# Sheet5.net
KiCad netlist of a schematic drawn in Altium Designer
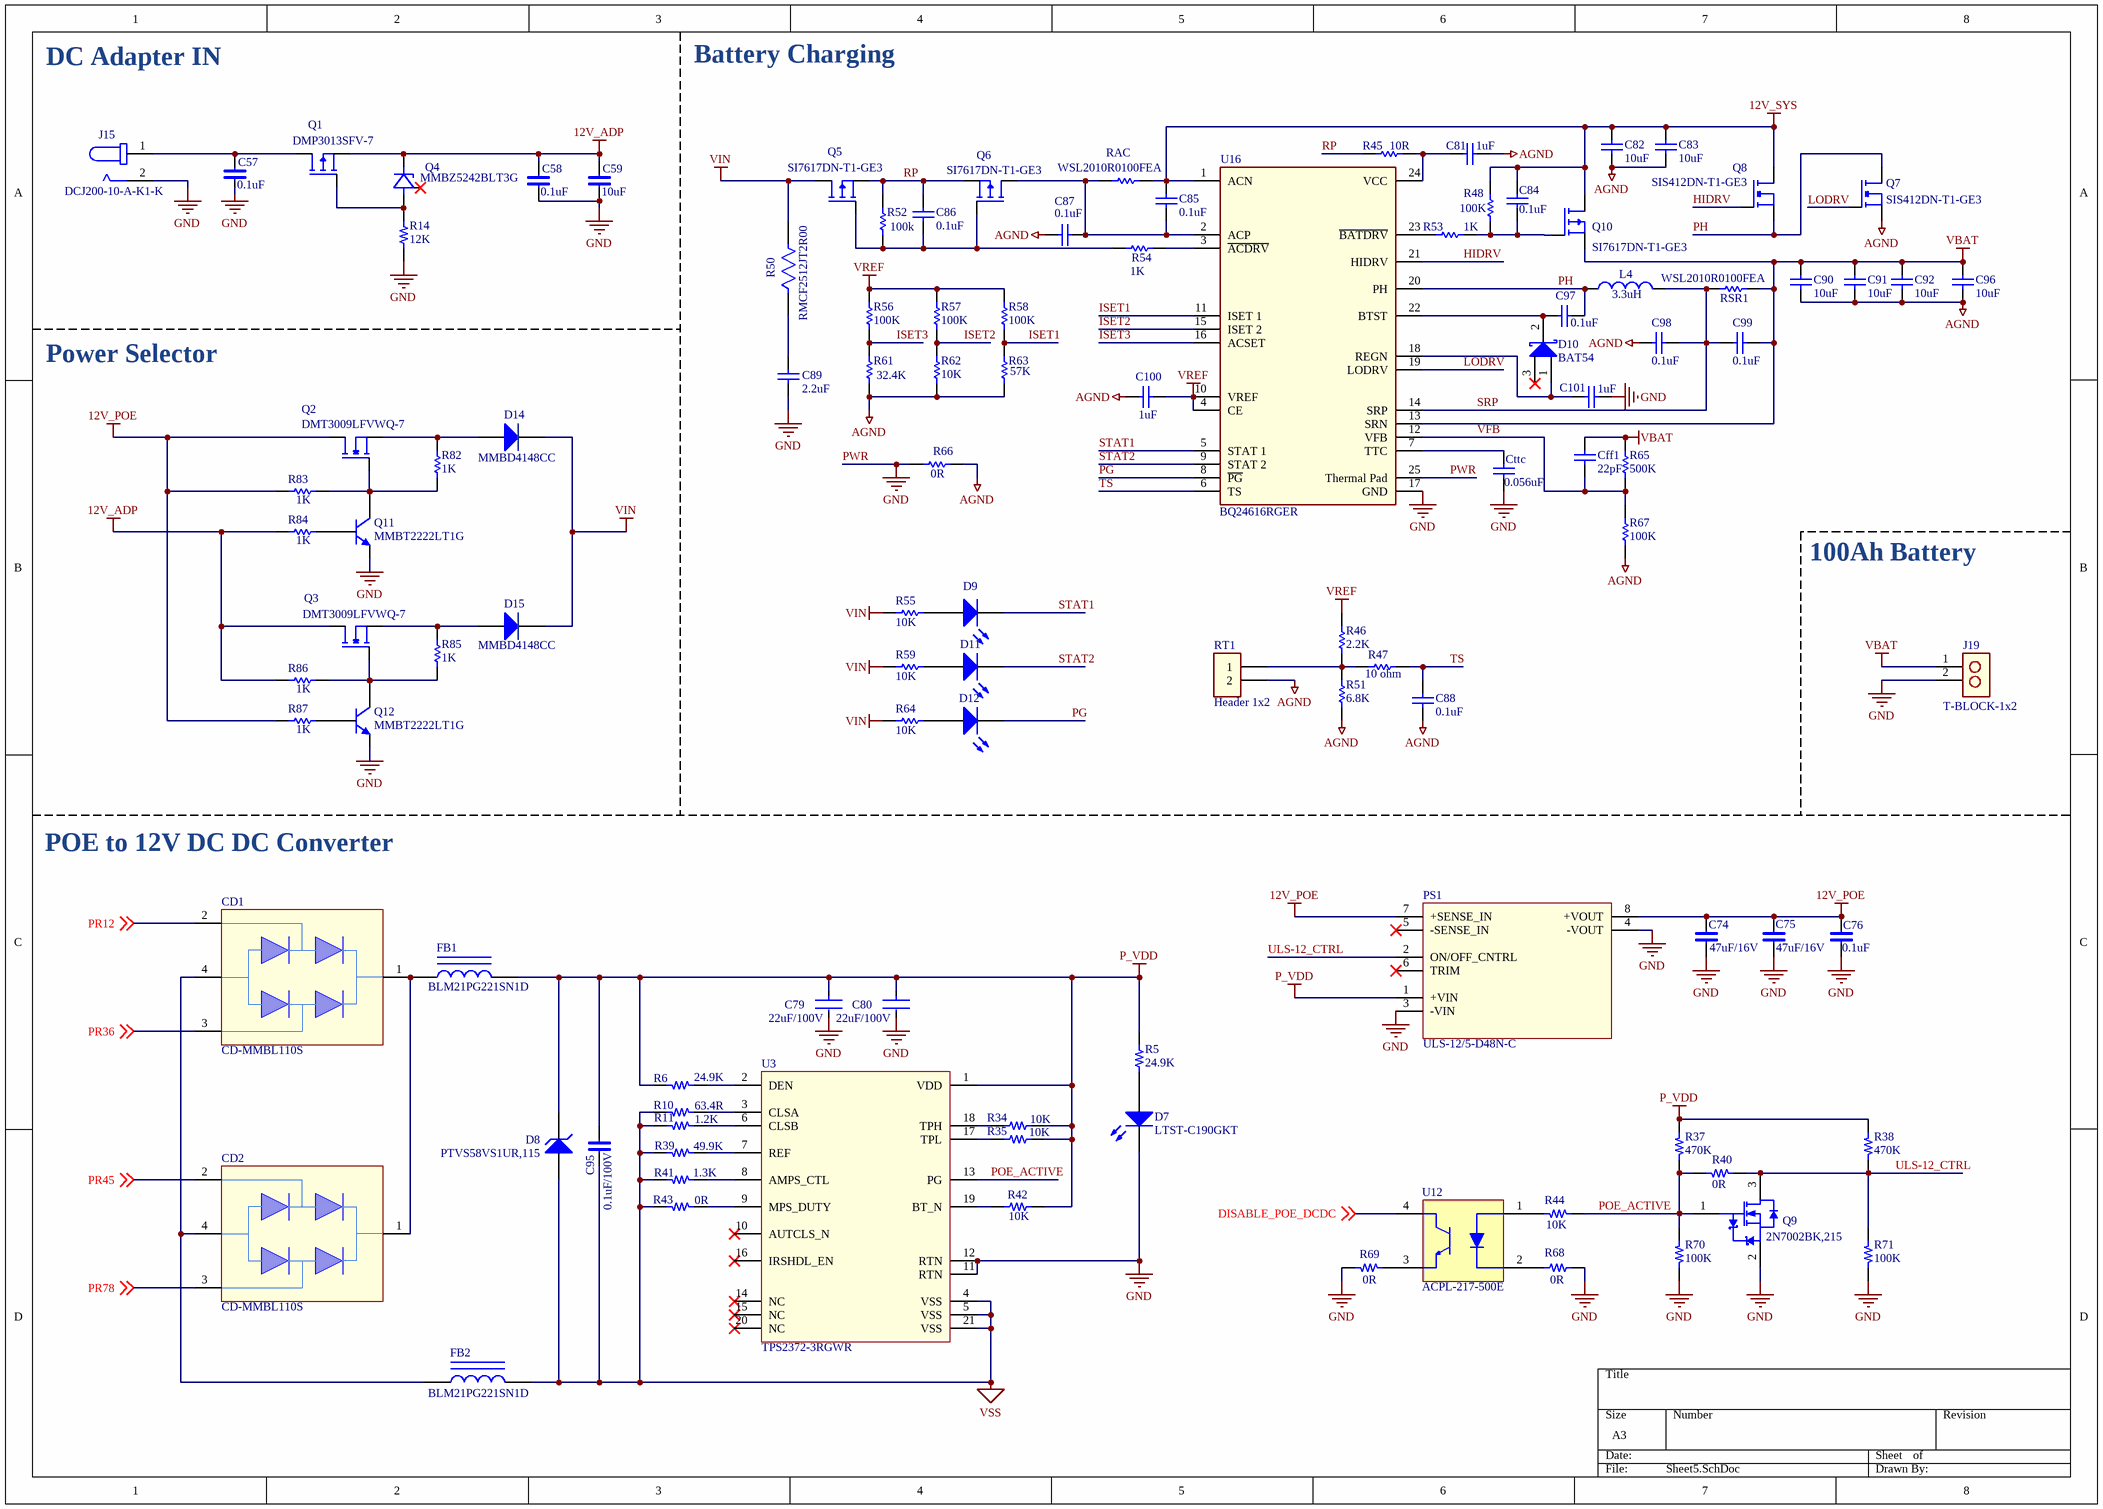
[diagram p0: Sheet5.SchDoc]

(export (version "E")
  (design (tool "Eeschema 10.0.6"))
  (components
    (comp (ref "C57")
      (value "0.1uF")
      (footprint "C-0603/1608")
      (description "CAP CER 10UF 10V X7R 0805")
      (fields (field (name "MFR. PART NO.") "GRM21BR71A106KA73K"))
      (libsource (lib "Custom_Library") (part "Capacitor-NonPolar"))
    )
    (comp (ref "C58")
      (value "0.1uF")
      (footprint "C-0603/1608")
      (description "CAP CER 10UF 10V X7R 0805")
      (fields (field (name "MFR. PART NO.") "GRM21BR71A106KA73K"))
      (libsource (lib "Custom_Library") (part "Capacitor-NonPolar"))
    )
    (comp (ref "C59")
      (value "10uF")
      (footprint "C-1206/3216")
      (description "CAP CER 10UF 10V X7R 0805")
      (fields (field (name "MFR. PART NO.") "GRM21BR71A106KA73K"))
      (libsource (lib "Custom_Library") (part "Capacitor-NonPolar"))
    )
    (comp (ref "C74")
      (value "47uF/16V")
      (footprint "C-1206/3216")
      (description "CAP CER 0.1UF 50V X7R 0402")
      (fields (field (name "MFR. PART NO.") "UMK105B7104KV-FR"))
      (libsource (lib "Custom_Library") (part "Capacitor-NonPolar"))
    )
    (comp (ref "C75")
      (value "47uF/16V")
      (footprint "C-1206/3216")
      (description "CAP CER 0.1UF 50V X7R 0402")
      (fields (field (name "MFR. PART NO.") "UMK105B7104KV-FR"))
      (libsource (lib "Custom_Library") (part "Capacitor-NonPolar"))
    )
    (comp (ref "C76")
      (value "0.1uF")
      (footprint "C-0402/1005")
      (description "CAP CER 0.1UF 50V X7R 0402")
      (fields (field (name "MFR. PART NO.") "UMK105B7104KV-FR"))
      (libsource (lib "Custom_Library") (part "Capacitor-NonPolar"))
    )
    (comp (ref "C79")
      (value "22uF/100V")
      (footprint "FP-KRM55W-6_1_5_3_6_7_1_2-MFG")
      (description "Cap Ceramic 22uF 100V X7R ±15% SMD 2220 +125°C Emboss T/R")
      (fields (field (name "TOLERANCE") "20%"))
      (libsource (lib "Altium Content Vault") (part "02cd4be3c70576c341d710602a673aa"))
    )
    (comp (ref "C80")
      (value "22uF/100V")
      (footprint "FP-KRM55W-6_1_5_3_6_7_1_2-MFG")
      (description "Cap Ceramic 22uF 100V X7R ±15% SMD 2220 +125°C Emboss T/R")
      (fields (field (name "TOLERANCE") "20%"))
      (libsource (lib "Altium Content Vault") (part "02cd4be3c70576c341d710602a673aa"))
    )
    (comp (ref "C81")
      (value "1uF")
      (footprint "C-0603/1608")
      (description "Capacitor")
      (fields (field (name "PUBLISHER") "Altium Limited"))
      (libsource (lib "Charger") (part "Capacitor"))
    )
    (comp (ref "C82")
      (value "10uF")
      (footprint "C-0805/2012")
      (description "Capacitor")
      (fields (field (name "PUBLISHER") "Altium Limited"))
      (libsource (lib "Charger") (part "Capacitor"))
    )
    (comp (ref "C83")
      (value "10uF")
      (footprint "C-0805/2012")
      (description "Capacitor")
      (fields (field (name "PUBLISHER") "Altium Limited"))
      (libsource (lib "Charger") (part "Capacitor"))
    )
    (comp (ref "C84")
      (value "0.1uF")
      (footprint "R-0402/1005")
      (description "Capacitor")
      (fields (field (name "PUBLISHER") "Altium Limited"))
      (libsource (lib "Charger") (part "Capacitor"))
    )
    (comp (ref "C85")
      (value "0.1uF")
      (footprint "C-0402/1005")
      (description "Capacitor")
      (fields (field (name "PUBLISHER") "Altium Limited"))
      (libsource (lib "Charger") (part "Capacitor"))
    )
    (comp (ref "C86")
      (value "0.1uF")
      (footprint "C-0402/1005")
      (description "Capacitor")
      (fields (field (name "PUBLISHER") "Altium Limited"))
      (libsource (lib "Charger") (part "Capacitor"))
    )
    (comp (ref "C87")
      (value "0.1uF")
      (footprint "C-0402/1005")
      (description "Capacitor")
      (fields (field (name "PUBLISHER") "Altium Limited"))
      (libsource (lib "Charger") (part "Capacitor"))
    )
    (comp (ref "C88")
      (value "0.1uF")
      (footprint "C-0402/1005")
      (description "Capacitor")
      (fields (field (name "PUBLISHER") "Altium Limited"))
      (libsource (lib "Charger") (part "Capacitor"))
    )
    (comp (ref "C89")
      (value "2.2uF")
      (footprint "C1206")
      (description "Capacitor")
      (fields (field (name "PUBLISHER") "Altium Limited"))
      (libsource (lib "Charger") (part "Capacitor"))
    )
    (comp (ref "C90")
      (value "10uF")
      (footprint "C-0805/2012")
      (description "Capacitor")
      (fields (field (name "PUBLISHER") "Altium Limited"))
      (libsource (lib "Charger") (part "Capacitor"))
    )
    (comp (ref "C91")
      (value "10uF")
      (footprint "C-0805/2012")
      (description "Capacitor")
      (fields (field (name "PUBLISHER") "Altium Limited"))
      (libsource (lib "Charger") (part "Capacitor"))
    )
    (comp (ref "C92")
      (value "10uF")
      (footprint "C-0805/2012")
      (description "Capacitor")
      (fields (field (name "PUBLISHER") "Altium Limited"))
      (libsource (lib "Charger") (part "Capacitor"))
    )
    (comp (ref "C95")
      (value "0.1uF/100V")
      (footprint "C-0402/1005")
      (description "CAP CER 0.1UF 50V X7R 0402")
      (fields (field (name "MFR. PART NO.") "UMK105B7104KV-FR"))
      (libsource (lib "Custom_Library") (part "Capacitor-NonPolar"))
    )
    (comp (ref "C96")
      (value "10uF")
      (footprint "C-0805/2012")
      (description "Capacitor")
      (fields (field (name "PUBLISHER") "Altium Limited"))
      (libsource (lib "Charger") (part "Capacitor"))
    )
    (comp (ref "C97")
      (value "0.1uF")
      (footprint "C-0402/1005")
      (description "Capacitor")
      (fields (field (name "PUBLISHER") "Altium Limited"))
      (libsource (lib "Charger") (part "Capacitor"))
    )
    (comp (ref "C98")
      (value "0.1uF")
      (footprint "C-0402/1005")
      (description "Capacitor")
      (fields (field (name "PUBLISHER") "Altium Limited"))
      (libsource (lib "Charger") (part "Capacitor"))
    )
    (comp (ref "C99")
      (value "0.1uF")
      (footprint "C-0402/1005")
      (description "Capacitor")
      (fields (field (name "PUBLISHER") "Altium Limited"))
      (libsource (lib "Charger") (part "Capacitor"))
    )
    (comp (ref "C100")
      (value "1uF")
      (footprint "C-0603/1608")
      (description "Capacitor")
      (fields (field (name "PUBLISHER") "Altium Limited"))
      (libsource (lib "Charger") (part "Capacitor"))
    )
    (comp (ref "C101")
      (value "1uF")
      (footprint "C-0603/1608")
      (description "Capacitor")
      (fields (field (name "PUBLISHER") "Altium Limited"))
      (libsource (lib "Charger") (part "Capacitor"))
    )
    (comp (ref "CD1")
      (value "CD-MMBL110S")
      (footprint "CD-MMBL110S")
      (libsource (lib "CD-MMBL110S") (part "CD-MMBL110S"))
    )
    (comp (ref "CD2")
      (value "CD-MMBL110S")
      (footprint "CD-MMBL110S")
      (libsource (lib "CD-MMBL110S") (part "CD-MMBL110S"))
    )
    (comp (ref "Cff1")
      (value "22pF")
      (footprint "C-0402/1005")
      (description "Capacitor")
      (fields (field (name "PUBLISHER") "Altium Limited"))
      (libsource (lib "Charger") (part "Capacitor"))
    )
    (comp (ref "Cttc")
      (value "0.056uF")
      (footprint "C-1206/3216")
      (description "Capacitor")
      (fields (field (name "PUBLISHER") "Altium Limited"))
      (libsource (lib "Charger") (part "Capacitor"))
    )
    (comp (ref "D7")
      (value "LTST-C190GKT")
      (footprint "LEDC1608X35N")
      (description "Typical INFRARED GaAs LED")
      (fields (field (name "PUBLISHER") "Altium Limited"))
      (libsource (lib "Miscellaneous Devices") (part "LED0"))
    )
    (comp (ref "D8")
      (value "PTVS58VS1UR,115")
      (footprint "DIO_PMEG4030ER,115")
      (description "Zener Diode")
      (fields (field (name "PUBLISHER") "Altium Limited"))
      (libsource (lib "Miscellaneous Devices") (part "D Zener"))
    )
    (comp (ref "D9")
      (value "LED")
      (footprint "LED-0402-GREEN")
      (description "Typical INFRARED GaAs LED")
      (fields (field (name "PUBLISHER") "Altium Limited"))
      (libsource (lib "Charger") (part "LED"))
    )
    (comp (ref "D10")
      (value "BAT54")
      (footprint "SOT-23-3")
      (description "Schottky Diode")
      (fields (field (name "PUBLISHER") "Altium Limited"))
      (libsource (lib "Battery Charger") (part "Diode Schottky_1"))
    )
    (comp (ref "D11")
      (value "LED")
      (footprint "LED-0402-GREEN")
      (description "Typical INFRARED GaAs LED")
      (fields (field (name "PUBLISHER") "Altium Limited"))
      (libsource (lib "Charger") (part "LED"))
    )
    (comp (ref "D12")
      (value "LED")
      (footprint "LED-0402-GREEN")
      (description "Typical INFRARED GaAs LED")
      (fields (field (name "PUBLISHER") "Altium Limited"))
      (libsource (lib "Charger") (part "LED"))
    )
    (comp (ref "D14")
      (value "MMBD4148CC")
      (footprint "SOT-23-3")
      (description "Diode GENERAL")
      (fields (field (name "PUBLISHER") "Altium Limited"))
      (libsource (lib "Battery Charger") (part "Diode GENERAL"))
    )
    (comp (ref "D15")
      (value "MMBD4148CC")
      (footprint "SOT-23-3")
      (description "Diode GENERAL")
      (fields (field (name "PUBLISHER") "Altium Limited"))
      (libsource (lib "Battery Charger") (part "Diode GENERAL"))
    )
    (comp (ref "FB1")
      (value "BLM21PG221SN1D")
      (footprint "BEADC2012X105N")
      (description "Magnetic-Core Inductor")
      (fields (field (name "PUBLISHER") "Altium Limited"))
      (libsource (lib "Miscellaneous Devices") (part "Inductor Iron"))
    )
    (comp (ref "FB2")
      (value "BLM21PG221SN1D")
      (footprint "BEADC2012X105N")
      (description "Magnetic-Core Inductor")
      (fields (field (name "PUBLISHER") "Altium Limited"))
      (libsource (lib "Miscellaneous Devices") (part "Inductor Iron"))
    )
    (comp (ref "J15")
      (value "DCJ200-10-A-K1-K")
      (footprint "GCT_DCJ200-10-A-XX-X_REVA")
      (description "CONN PWR JACK 2X5.5MM SOLDER")
      (fields (field (name "MFR. PART NO.") "PJ-037AH"))
      (libsource (lib "Custom_Library") (part "DC Jack"))
    )
    (comp (ref "J19")
      (value "T-BLOCK-1x2")
      (footprint "Terminal Block-1x2-5.08mm")
      (libsource (lib "Custom_Library") (part "T-BLOCK-1x2"))
    )
    (comp (ref "L4")
      (value "3.3uH")
      (footprint "IND_SRN6045TA-3R3Y")
      (description "Inductor")
      (fields (field (name "PUBLISHER") "Altium Limited"))
      (libsource (lib "Charger") (part "Inductor"))
    )
    (comp (ref "PS1")
      (value "ULS-12/5-D48N-C")
      (footprint "CONV_ULS-12/5-D48N-C")
      (description "Isolated Module DC DC Converter 1 Output 12V - - 5A 36V - 75V Input")
      (fields (field (name "MF") "Murata Power Solutions Inc."))
      (libsource (lib "ULS-12_5-D48N-C") (part "ULS-12/5-D48N-C"))
    )
    (comp (ref "Q1")
      (value "DMP3013SFV-7")
      (footprint "POWERDI3333-8_UX_DIO")
      (libsource (lib "Custom_Library") (part "MOSFET-P"))
    )
    (comp (ref "Q2")
      (value "DMT3009LFVWQ-7")
      (footprint "POWERDI3333-8_UX_DIO")
      (libsource (lib "Custom_Library") (part "MOSFET-N"))
    )
    (comp (ref "Q3")
      (value "DMT3009LFVWQ-7")
      (footprint "POWERDI3333-8_UX_DIO")
      (libsource (lib "Custom_Library") (part "MOSFET-N"))
    )
    (comp (ref "Q4")
      (value "MMBZ5242BLT3G")
      (footprint "SOT-23-3")
      (libsource (lib "Custom_Library") (part "Diode-SOT23-3"))
    )
    (comp (ref "Q5")
      (value "SI7617DN-T1-GE3")
      (footprint "POWERDI3333-8_UX_DIO")
      (libsource (lib "Custom_Library") (part "MOSFET-P"))
    )
    (comp (ref "Q6")
      (value "SI7617DN-T1-GE3")
      (footprint "POWERDI3333-8_UX_DIO")
      (libsource (lib "Custom_Library") (part "MOSFET-P"))
    )
    (comp (ref "Q7")
      (value "SIS412DN-T1-GE3")
      (footprint "POWERDI3333-8_UX_DIO")
      (libsource (lib "Custom_Library") (part "MOSFET-N"))
    )
    (comp (ref "Q8")
      (value "SIS412DN-T1-GE3")
      (footprint "POWERDI3333-8_UX_DIO")
      (libsource (lib "Custom_Library") (part "MOSFET-N"))
    )
    (comp (ref "Q9")
      (value "2N7002BK,215")
      (footprint "NXP-SOT23_M")
      (description "N-Channel Trench MOSFET, 60 V, 0.35 A, -55 to 150 degC, 3-Pin SOT23, Tape and Reel")
      (fields (field (name "MANUFACTURER") "NXP Semiconductors"))
      (libsource (lib "Altium Content Vault") (part "NXP-NMOS-GSD-3_A"))
    )
    (comp (ref "Q10")
      (value "SI7617DN-T1-GE3")
      (footprint "POWERDI3333-8_UX_DIO")
      (libsource (lib "Custom_Library") (part "MOSFET-P"))
    )
    (comp (ref "Q11")
      (value "MMBT2222LT1G")
      (footprint "SOT-23-3")
      (description "NPN General Purpose Amplifier")
      (fields (field (name "PUBLISHER") "Altium Limited"))
      (libsource (lib "Miscellaneous Devices") (part "2N3904"))
    )
    (comp (ref "Q12")
      (value "MMBT2222LT1G")
      (footprint "SOT-23-3")
      (description "NPN General Purpose Amplifier")
      (fields (field (name "PUBLISHER") "Altium Limited"))
      (libsource (lib "Miscellaneous Devices") (part "2N3904"))
    )
    (comp (ref "R5")
      (value "24.9K")
      (footprint "R-0402/1005")
      (description "RES SMD 15K OHM 1% 1/16W 0402")
      (fields (field (name "MFR. PART NO.") "MCR01MZPF1502"))
      (libsource (lib "Custom_Library") (part "Resistor"))
    )
    (comp (ref "R6")
      (value "24.9K")
      (footprint "R-0402/1005")
      (description "RES SMD 15K OHM 1% 1/16W 0402")
      (fields (field (name "MFR. PART NO.") "MCR01MZPF1502"))
      (libsource (lib "Custom_Library") (part "Resistor"))
    )
    (comp (ref "R10")
      (value "63.4R")
      (footprint "R-0402/1005")
      (description "RES SMD 15K OHM 1% 1/16W 0402")
      (fields (field (name "MFR. PART NO.") "MCR01MZPF1502"))
      (libsource (lib "Custom_Library") (part "Resistor"))
    )
    (comp (ref "R11")
      (value "1.2K")
      (footprint "R-0402/1005")
      (description "RES SMD 15K OHM 1% 1/16W 0402")
      (fields (field (name "MFR. PART NO.") "MCR01MZPF1502"))
      (libsource (lib "Custom_Library") (part "Resistor"))
    )
    (comp (ref "R14")
      (value "12K")
      (footprint "R-0402/1005")
      (description "RES SMD 51 OHM 0.5% 1/16W 0402")
      (fields (field (name "MFR. PART NO.") "ERA-2AED510X"))
      (libsource (lib "Custom_Library") (part "Resistor"))
    )
    (comp (ref "R34")
      (value "10K")
      (footprint "R-0402/1005")
      (description "RES SMD 15K OHM 1% 1/16W 0402")
      (fields (field (name "MFR. PART NO.") "MCR01MZPF1502"))
      (libsource (lib "Custom_Library") (part "Resistor"))
    )
    (comp (ref "R35")
      (value "10K")
      (footprint "R-0402/1005")
      (description "RES SMD 15K OHM 1% 1/16W 0402")
      (fields (field (name "MFR. PART NO.") "MCR01MZPF1502"))
      (libsource (lib "Custom_Library") (part "Resistor"))
    )
    (comp (ref "R37")
      (value "470K")
      (footprint "R-0402/1005")
      (description "RES SMD 15K OHM 1% 1/16W 0402")
      (fields (field (name "MFR. PART NO.") "MCR01MZPF1502"))
      (libsource (lib "Custom_Library") (part "Resistor"))
    )
    (comp (ref "R38")
      (value "470K")
      (footprint "R-0402/1005")
      (description "RES SMD 15K OHM 1% 1/16W 0402")
      (fields (field (name "MFR. PART NO.") "MCR01MZPF1502"))
      (libsource (lib "Custom_Library") (part "Resistor"))
    )
    (comp (ref "R39")
      (value "49.9K")
      (footprint "R-0402/1005")
      (description "RES SMD 15K OHM 1% 1/16W 0402")
      (fields (field (name "MFR. PART NO.") "MCR01MZPF1502"))
      (libsource (lib "Custom_Library") (part "Resistor"))
    )
    (comp (ref "R40")
      (value "0R")
      (footprint "R-0402/1005")
      (description "RES SMD 15K OHM 1% 1/16W 0402")
      (fields (field (name "MFR. PART NO.") "MCR01MZPF1502"))
      (libsource (lib "Custom_Library") (part "Resistor"))
    )
    (comp (ref "R41")
      (value "1.3K")
      (footprint "R-0402/1005")
      (description "RES SMD 15K OHM 1% 1/16W 0402")
      (fields (field (name "MFR. PART NO.") "MCR01MZPF1502"))
      (libsource (lib "Custom_Library") (part "Resistor"))
    )
    (comp (ref "R42")
      (value "10K")
      (footprint "R-0402/1005")
      (description "RES SMD 15K OHM 1% 1/16W 0402")
      (fields (field (name "MFR. PART NO.") "MCR01MZPF1502"))
      (libsource (lib "Custom_Library") (part "Resistor"))
    )
    (comp (ref "R43")
      (value "0R")
      (footprint "R-0402/1005")
      (description "RES SMD 15K OHM 1% 1/16W 0402")
      (fields (field (name "MFR. PART NO.") "MCR01MZPF1502"))
      (libsource (lib "Custom_Library") (part "Resistor"))
    )
    (comp (ref "R44")
      (value "10K")
      (footprint "R-0402/1005")
      (description "RES SMD 15K OHM 1% 1/16W 0402")
      (fields (field (name "MFR. PART NO.") "MCR01MZPF1502"))
      (libsource (lib "Custom_Library") (part "Resistor"))
    )
    (comp (ref "R45")
      (value "10R")
      (footprint "R-0805/2012")
      (description "Semiconductor Resistor")
      (fields (field (name "Comment") "Resistor") (field (name "PUBLISHER") "Altium Limited"))
      (libsource (lib "Charger") (part "Resistor"))
    )
    (comp (ref "R46")
      (value "2.2K")
      (footprint "R-0402/1005")
      (description "Semiconductor Resistor")
      (fields (field (name "Comment") "Resistor") (field (name "PUBLISHER") "Altium Limited"))
      (libsource (lib "Charger") (part "Resistor"))
    )
    (comp (ref "R47")
      (value "10 ohm")
      (footprint "R-0402/1005")
      (description "Semiconductor Resistor")
      (fields (field (name "Comment") "Resistor") (field (name "PUBLISHER") "Altium Limited"))
      (libsource (lib "Charger") (part "Resistor"))
    )
    (comp (ref "R48")
      (value "100K")
      (footprint "R-0402/1005")
      (description "Semiconductor Resistor")
      (fields (field (name "Comment") "Resistor") (field (name "PUBLISHER") "Altium Limited"))
      (libsource (lib "Charger") (part "Resistor"))
    )
    (comp (ref "R50")
      (value "RMCF2512JT2R00")
      (footprint "FP-RMCF2512-IPC_A")
      (description "2Ω ±5% 1W 2512 Thick Film Chip Resistor AEC-Q200 compliant")
      (fields (field (name "TOLERANCE") "5%"))
      (libsource (lib "Altium Content Vault") (part "1029c3af85768c4190bb7ad29bc67b5"))
    )
    (comp (ref "R51")
      (value "6.8K")
      (footprint "R-0402/1005")
      (description "Semiconductor Resistor")
      (fields (field (name "Comment") "Resistor") (field (name "PUBLISHER") "Altium Limited"))
      (libsource (lib "Charger") (part "Resistor"))
    )
    (comp (ref "R52")
      (value "100k")
      (footprint "R-0402/1005")
      (description "Semiconductor Resistor")
      (fields (field (name "Comment") "Resistor") (field (name "PUBLISHER") "Altium Limited"))
      (libsource (lib "Charger") (part "Resistor"))
    )
    (comp (ref "R53")
      (value "1K")
      (footprint "R-0402/1005")
      (description "Semiconductor Resistor")
      (fields (field (name "Comment") "Resistor") (field (name "PUBLISHER") "Altium Limited"))
      (libsource (lib "Charger") (part "Resistor"))
    )
    (comp (ref "R54")
      (value "1K")
      (footprint "R-0402/1005")
      (description "Resistor")
      (fields (field (name "PUBLISHER") "Altium Limited"))
      (libsource (lib "Battery Charger") (part "Res1"))
    )
    (comp (ref "R55")
      (value "10K")
      (footprint "R-0402/1005")
      (description "Semiconductor Resistor")
      (fields (field (name "Comment") "Resistor") (field (name "PUBLISHER") "Altium Limited"))
      (libsource (lib "Charger") (part "Resistor"))
    )
    (comp (ref "R56")
      (value "100K")
      (footprint "R-0402/1005")
      (description "Semiconductor Resistor")
      (fields (field (name "Comment") "Resistor") (field (name "PUBLISHER") "Altium Limited"))
      (libsource (lib "Charger") (part "Resistor"))
    )
    (comp (ref "R57")
      (value "100K")
      (footprint "R-0402/1005")
      (description "Semiconductor Resistor")
      (fields (field (name "Comment") "Resistor") (field (name "PUBLISHER") "Altium Limited"))
      (libsource (lib "Charger") (part "Resistor"))
    )
    (comp (ref "R58")
      (value "100K")
      (footprint "R-0402/1005")
      (description "Semiconductor Resistor")
      (fields (field (name "Comment") "Resistor") (field (name "PUBLISHER") "Altium Limited"))
      (libsource (lib "Charger") (part "Resistor"))
    )
    (comp (ref "R59")
      (value "10K")
      (footprint "R-0402/1005")
      (description "Semiconductor Resistor")
      (fields (field (name "Comment") "Resistor") (field (name "PUBLISHER") "Altium Limited"))
      (libsource (lib "Charger") (part "Resistor"))
    )
    (comp (ref "R61")
      (value "32.4K")
      (footprint "R-0402/1005")
      (description "Semiconductor Resistor")
      (fields (field (name "Comment") "Resistor") (field (name "PUBLISHER") "Altium Limited"))
      (libsource (lib "Charger") (part "Resistor"))
    )
    (comp (ref "R62")
      (value "10K")
      (footprint "R-0402/1005")
      (description "Semiconductor Resistor")
      (fields (field (name "Comment") "Resistor") (field (name "PUBLISHER") "Altium Limited"))
      (libsource (lib "Charger") (part "Resistor"))
    )
    (comp (ref "R63")
      (value "57K")
      (footprint "R-0402/1005")
      (description "Semiconductor Resistor")
      (fields (field (name "Comment") "Resistor") (field (name "PUBLISHER") "Altium Limited"))
      (libsource (lib "Charger") (part "Resistor"))
    )
    (comp (ref "R64")
      (value "10K")
      (footprint "R-0402/1005")
      (description "Semiconductor Resistor")
      (fields (field (name "Comment") "Resistor") (field (name "PUBLISHER") "Altium Limited"))
      (libsource (lib "Charger") (part "Resistor"))
    )
    (comp (ref "R65")
      (value "500K")
      (footprint "R-0402/1005")
      (description "Semiconductor Resistor")
      (fields (field (name "Comment") "Resistor") (field (name "PUBLISHER") "Altium Limited"))
      (libsource (lib "Charger") (part "Resistor"))
    )
    (comp (ref "R66")
      (value "0R")
      (footprint "R-1210")
      (description "Semiconductor Resistor")
      (fields (field (name "Comment") "Resistor") (field (name "PUBLISHER") "Altium Limited"))
      (libsource (lib "Charger") (part "Resistor"))
    )
    (comp (ref "R67")
      (value "100K")
      (footprint "R-0402/1005")
      (description "Semiconductor Resistor")
      (fields (field (name "Comment") "Resistor") (field (name "PUBLISHER") "Altium Limited"))
      (libsource (lib "Charger") (part "Resistor"))
    )
    (comp (ref "R68")
      (value "0R")
      (footprint "R-0402/1005")
      (description "RES SMD 15K OHM 1% 1/16W 0402")
      (fields (field (name "MFR. PART NO.") "MCR01MZPF1502"))
      (libsource (lib "Custom_Library") (part "Resistor"))
    )
    (comp (ref "R69")
      (value "0R")
      (footprint "R-0402/1005")
      (description "RES SMD 15K OHM 1% 1/16W 0402")
      (fields (field (name "MFR. PART NO.") "MCR01MZPF1502"))
      (libsource (lib "Custom_Library") (part "Resistor"))
    )
    (comp (ref "R70")
      (value "100K")
      (footprint "R-0402/1005")
      (description "RES SMD 15K OHM 1% 1/16W 0402")
      (fields (field (name "MFR. PART NO.") "MCR01MZPF1502"))
      (libsource (lib "Custom_Library") (part "Resistor"))
    )
    (comp (ref "R71")
      (value "100K")
      (footprint "R-0402/1005")
      (description "RES SMD 15K OHM 1% 1/16W 0402")
      (fields (field (name "MFR. PART NO.") "MCR01MZPF1502"))
      (libsource (lib "Custom_Library") (part "Resistor"))
    )
    (comp (ref "R82")
      (value "1K")
      (footprint "R-0402/1005")
      (description "Semiconductor Resistor")
      (fields (field (name "PUBLISHER") "Altium Limited"))
      (libsource (lib "Battery Charger") (part "Resistor"))
    )
    (comp (ref "R83")
      (value "1K")
      (footprint "R-0402/1005")
      (description "Semiconductor Resistor")
      (fields (field (name "PUBLISHER") "Altium Limited"))
      (libsource (lib "Battery Charger") (part "Resistor"))
    )
    (comp (ref "R84")
      (value "1K")
      (footprint "R-0402/1005")
      (description "Semiconductor Resistor")
      (fields (field (name "PUBLISHER") "Altium Limited"))
      (libsource (lib "Battery Charger") (part "Resistor"))
    )
    (comp (ref "R85")
      (value "1K")
      (footprint "R-0402/1005")
      (description "Semiconductor Resistor")
      (fields (field (name "PUBLISHER") "Altium Limited"))
      (libsource (lib "Battery Charger") (part "Resistor"))
    )
    (comp (ref "R86")
      (value "1K")
      (footprint "R-0402/1005")
      (description "Semiconductor Resistor")
      (fields (field (name "PUBLISHER") "Altium Limited"))
      (libsource (lib "Battery Charger") (part "Resistor"))
    )
    (comp (ref "R87")
      (value "1K")
      (footprint "R-0402/1005")
      (description "Semiconductor Resistor")
      (fields (field (name "PUBLISHER") "Altium Limited"))
      (libsource (lib "Battery Charger") (part "Resistor"))
    )
    (comp (ref "RAC")
      (value "WSL2010R0100FEA")
      (footprint "RESC5125X89X51LL25T25")
      (description "Chip Resistor, 10 mOhm, +/- 1%, 0.5 W, -65 to 170 degC, 2010 (5025 Metric), RoHS, Tape and Reel")
      (fields (field (name "MANUFACTURER") "Vishay") (field (name "TOLERANCE") "1%"))
      (libsource (lib "Altium Content Vault") (part "RES-2"))
    )
    (comp (ref "RSR1")
      (value "WSL2010R0100FEA")
      (footprint "RESC5125X89X51LL25T25")
      (description "Chip Resistor, 10 mOhm, +/- 1%, 0.5 W, -65 to 170 degC, 2010 (5025 Metric), RoHS, Tape and Reel")
      (fields (field (name "MANUFACTURER") "Vishay") (field (name "TOLERANCE") "1%"))
      (libsource (lib "Altium Content Vault") (part "RES-2"))
    )
    (comp (ref "RT1")
      (value "Header 1x2")
      (footprint "PIN HEADER 1x2 2.54mm")
      (description "CONN HEADER VERT 3POS 2.54MM")
      (fields (field (name "MFR. PART NO.") "75160-156-03LF"))
      (libsource (lib "Custom_Library") (part "Header 1x2"))
    )
    (comp (ref "U3")
      (value "TPS2372-3RGWR")
      (footprint "QFN65P500X500X100-21N")
      (description "No Description Available")
      (fields (field (name "COPYRIGHT") "Copyright (C) 2023 Ultra Librarian. All rights reserved."))
      (libsource (lib "TPS2372-3RGWR") (part "TPS2372-3RGWR"))
    )
    (comp (ref "U12")
      (value "ACPL-217-500E")
      (footprint "AVAG-ACPL-217-4_M")
      (fields (field (name "MANUFACTURER") "AvagoTechnologies"))
      (libsource (lib "Altium Content Vault") (part "AVAG-ACPL-217-4"))
    )
    (comp (ref "U16")
      (value "BQ24616RGER")
      (footprint "QFN50P400X400X100-25N")
      (libsource (lib "BATTERY CHARGER FINAL SCH") (part "bq24616"))
    )
  )
  (nets
    (net (code "1") (name "/HIDRV") (class "Default")
      (node (ref "Q8") (pin "G") (pinfunction "G_G") (pintype "passive"))
      (node (ref "U16") (pin "21") (pinfunction "HIDRV_21") (pintype "passive"))
    )
    (net (code "2") (name "/ISET1") (class "Default")
      (node (ref "R58") (pin "2") (pinfunction "2_2") (pintype "passive"))
      (node (ref "R63") (pin "1") (pinfunction "1_1") (pintype "passive"))
      (node (ref "U16") (pin "11") (pinfunction "ISET_1_11") (pintype "passive"))
    )
    (net (code "3") (name "/ISET2") (class "Default")
      (node (ref "R57") (pin "2") (pinfunction "2_2") (pintype "passive"))
      (node (ref "R62") (pin "1") (pinfunction "1_1") (pintype "passive"))
      (node (ref "U16") (pin "15") (pinfunction "ISET_2_15") (pintype "passive"))
    )
    (net (code "4") (name "/ISET3") (class "Default")
      (node (ref "R56") (pin "2") (pinfunction "2_2") (pintype "passive"))
      (node (ref "R61") (pin "1") (pinfunction "1_1") (pintype "passive"))
      (node (ref "U16") (pin "16") (pinfunction "ACSET_16") (pintype "passive"))
    )
    (net (code "5") (name "/LODRV") (class "Default")
      (node (ref "Q7") (pin "G") (pinfunction "G_G") (pintype "passive"))
      (node (ref "U16") (pin "19") (pinfunction "LODRV_19") (pintype "passive"))
    )
    (net (code "6") (name "/PG") (class "Default")
      (node (ref "D12") (pin "2") (pinfunction "2_2") (pintype "passive"))
      (node (ref "U16") (pin "8") (pinfunction "~{PG}_8") (pintype "passive"))
    )
    (net (code "7") (name "/PH") (class "Default")
      (node (ref "C97") (pin "1") (pinfunction "1_1") (pintype "passive"))
      (node (ref "L4") (pin "1") (pinfunction "1_1") (pintype "passive"))
      (node (ref "Q7") (pin "D") (pinfunction "D_D") (pintype "passive"))
      (node (ref "Q8") (pin "S") (pinfunction "S_S") (pintype "passive"))
      (node (ref "U16") (pin "20") (pinfunction "PH_20") (pintype "passive"))
    )
    (net (code "8") (name "/POE_ACTIVE") (class "Default")
      (node (ref "Q9") (pin "1") (pinfunction "G_1") (pintype "passive"))
      (node (ref "R37") (pin "2") (pinfunction "2_2") (pintype "passive"))
      (node (ref "R40") (pin "1") (pinfunction "1_1") (pintype "passive"))
      (node (ref "R44") (pin "1") (pinfunction "1_1") (pintype "passive"))
      (node (ref "R70") (pin "1") (pinfunction "1_1") (pintype "passive"))
      (node (ref "U3") (pin "13") (pinfunction "PG_13") (pintype "passive"))
    )
    (net (code "9") (name "/RP") (class "Default")
      (node (ref "C86") (pin "2") (pinfunction "2_2") (pintype "passive"))
      (node (ref "Q5") (pin "S") (pinfunction "S_S") (pintype "passive"))
      (node (ref "Q6") (pin "S") (pinfunction "S_S") (pintype "passive"))
      (node (ref "R45") (pin "1") (pinfunction "1_1") (pintype "passive"))
      (node (ref "R52") (pin "2") (pinfunction "2_2") (pintype "passive"))
    )
    (net (code "10") (name "/SRP") (class "Default")
      (node (ref "C98") (pin "1") (pinfunction "1_1") (pintype "passive"))
      (node (ref "C99") (pin "2") (pinfunction "2_2") (pintype "passive"))
      (node (ref "L4") (pin "2") (pinfunction "2_2") (pintype "passive"))
      (node (ref "RSR1") (pin "1") (pinfunction "1_1") (pintype "passive"))
      (node (ref "U16") (pin "14") (pinfunction "SRP_14") (pintype "passive"))
    )
    (net (code "11") (name "/STAT1") (class "Default")
      (node (ref "D9") (pin "2") (pinfunction "2_2") (pintype "passive"))
      (node (ref "U16") (pin "5") (pinfunction "STAT_1_5") (pintype "passive"))
    )
    (net (code "12") (name "/STAT2") (class "Default")
      (node (ref "D11") (pin "2") (pinfunction "2_2") (pintype "passive"))
      (node (ref "U16") (pin "9") (pinfunction "STAT_2_9") (pintype "passive"))
    )
    (net (code "13") (name "/TS") (class "Default")
      (node (ref "C88") (pin "2") (pinfunction "2_2") (pintype "passive"))
      (node (ref "R47") (pin "1") (pinfunction "1_1") (pintype "passive"))
      (node (ref "U16") (pin "6") (pinfunction "TS_6") (pintype "passive"))
    )
    (net (code "14") (name "/ULS-12_CTRL") (class "Default")
      (node (ref "PS1") (pin "2") (pinfunction "ON/OFF_CNTRL_2") (pintype "passive"))
      (node (ref "Q9") (pin "3") (pinfunction "D_3") (pintype "passive"))
      (node (ref "R38") (pin "2") (pinfunction "2_2") (pintype "passive"))
      (node (ref "R40") (pin "2") (pinfunction "2_2") (pintype "passive"))
      (node (ref "R71") (pin "1") (pinfunction "1_1") (pintype "passive"))
    )
    (net (code "15") (name "/VFB") (class "Default")
      (node (ref "Cff1") (pin "1") (pinfunction "1_1") (pintype "passive"))
      (node (ref "R65") (pin "1") (pinfunction "1_1") (pintype "passive"))
      (node (ref "R67") (pin "2") (pinfunction "2_2") (pintype "passive"))
      (node (ref "U16") (pin "12") (pinfunction "VFB_12") (pintype "passive"))
    )
    (net (code "16") (name "12V_ADP") (class "Default")
      (node (ref "C58") (pin "1") (pinfunction "1_1") (pintype "passive"))
      (node (ref "C59") (pin "1") (pinfunction "1_1") (pintype "passive"))
      (node (ref "Q1") (pin "S") (pinfunction "S_S") (pintype "passive"))
      (node (ref "Q3") (pin "D") (pinfunction "D_D") (pintype "passive"))
      (node (ref "Q4") (pin "3") (pinfunction "3_3") (pintype "passive"))
      (node (ref "R84") (pin "1") (pinfunction "1_1") (pintype "passive"))
      (node (ref "R86") (pin "1") (pinfunction "1_1") (pintype "passive"))
    )
    (net (code "17") (name "12V_POE") (class "Default")
      (node (ref "C74") (pin "1") (pinfunction "1_1") (pintype "passive"))
      (node (ref "C75") (pin "1") (pinfunction "1_1") (pintype "passive"))
      (node (ref "C76") (pin "1") (pinfunction "1_1") (pintype "passive"))
      (node (ref "PS1") (pin "7") (pinfunction "+SENSE_IN_7") (pintype "passive"))
      (node (ref "PS1") (pin "8") (pinfunction "+VOUT_8") (pintype "passive"))
      (node (ref "Q2") (pin "D") (pinfunction "D_D") (pintype "passive"))
      (node (ref "R83") (pin "1") (pinfunction "1_1") (pintype "passive"))
      (node (ref "R87") (pin "1") (pinfunction "1_1") (pintype "passive"))
    )
    (net (code "18") (name "12V_SYS") (class "Default")
      (node (ref "C82") (pin "1") (pinfunction "1_1") (pintype "passive"))
      (node (ref "C83") (pin "1") (pinfunction "1_1") (pintype "passive"))
      (node (ref "C84") (pin "2") (pinfunction "2_2") (pintype "passive"))
      (node (ref "C85") (pin "2") (pinfunction "2_2") (pintype "passive"))
      (node (ref "Q10") (pin "D") (pinfunction "D_D") (pintype "passive"))
      (node (ref "Q8") (pin "D") (pinfunction "D_D") (pintype "passive"))
      (node (ref "R48") (pin "2") (pinfunction "2_2") (pintype "passive"))
      (node (ref "RAC") (pin "2") (pinfunction "2_2") (pintype "passive"))
      (node (ref "U16") (pin "1") (pinfunction "ACN_1") (pintype "passive"))
    )
    (net (code "19") (name "AGND") (class "Default")
      (node (ref "C100") (pin "1") (pinfunction "1_1") (pintype "passive"))
      (node (ref "C81") (pin "2") (pinfunction "2_2") (pintype "passive"))
      (node (ref "C82") (pin "2") (pinfunction "2_2") (pintype "passive"))
      (node (ref "C83") (pin "2") (pinfunction "2_2") (pintype "passive"))
      (node (ref "C87") (pin "1") (pinfunction "1_1") (pintype "passive"))
      (node (ref "C88") (pin "1") (pinfunction "1_1") (pintype "passive"))
      (node (ref "C90") (pin "2") (pinfunction "2_2") (pintype "passive"))
      (node (ref "C91") (pin "2") (pinfunction "2_2") (pintype "passive"))
      (node (ref "C92") (pin "2") (pinfunction "2_2") (pintype "passive"))
      (node (ref "C96") (pin "2") (pinfunction "2_2") (pintype "passive"))
      (node (ref "C98") (pin "2") (pinfunction "2_2") (pintype "passive"))
      (node (ref "Q7") (pin "S") (pinfunction "S_S") (pintype "passive"))
      (node (ref "R51") (pin "2") (pinfunction "2_2") (pintype "passive"))
      (node (ref "R61") (pin "2") (pinfunction "2_2") (pintype "passive"))
      (node (ref "R62") (pin "2") (pinfunction "2_2") (pintype "passive"))
      (node (ref "R63") (pin "2") (pinfunction "2_2") (pintype "passive"))
      (node (ref "R66") (pin "1") (pinfunction "1_1") (pintype "passive"))
      (node (ref "R67") (pin "1") (pinfunction "1_1") (pintype "passive"))
      (node (ref "RT1") (pin "2") (pinfunction "2_2") (pintype "passive"))
    )
    (net (code "20") (name "DISABLE_POE_DCDC") (class "Default")
      (node (ref "U12") (pin "4") (pinfunction "COLLECTOR_4") (pintype "passive"))
    )
    (net (code "21") (name "GND") (class "Default")
      (node (ref "C101") (pin "2") (pinfunction "2_2") (pintype "passive"))
      (node (ref "C57") (pin "2") (pinfunction "2_2") (pintype "passive"))
      (node (ref "C58") (pin "2") (pinfunction "2_2") (pintype "passive"))
      (node (ref "C59") (pin "2") (pinfunction "2_2") (pintype "passive"))
      (node (ref "C74") (pin "2") (pinfunction "2_2") (pintype "passive"))
      (node (ref "C75") (pin "2") (pinfunction "2_2") (pintype "passive"))
      (node (ref "C76") (pin "2") (pinfunction "2_2") (pintype "passive"))
      (node (ref "C79") (pin "2") (pinfunction "2_2") (pintype "passive"))
      (node (ref "C80") (pin "2") (pinfunction "2_2") (pintype "passive"))
      (node (ref "C89") (pin "1") (pinfunction "1_1") (pintype "passive"))
      (node (ref "Cttc") (pin "2") (pinfunction "2_2") (pintype "passive"))
      (node (ref "D7") (pin "C") (pinfunction "C_C") (pintype "passive"))
      (node (ref "J15") (pin "2") (pinfunction "2_2") (pintype "passive"))
      (node (ref "J19") (pin "2") (pinfunction "2_2") (pintype "passive"))
      (node (ref "PS1") (pin "3") (pinfunction "-VIN_3") (pintype "passive"))
      (node (ref "PS1") (pin "4") (pinfunction "-VOUT_4") (pintype "passive"))
      (node (ref "Q11") (pin "1") (pinfunction "E_1") (pintype "passive"))
      (node (ref "Q12") (pin "1") (pinfunction "E_1") (pintype "passive"))
      (node (ref "Q9") (pin "2") (pinfunction "S_2") (pintype "passive"))
      (node (ref "R14") (pin "1") (pinfunction "1_1") (pintype "passive"))
      (node (ref "R66") (pin "2") (pinfunction "2_2") (pintype "passive"))
      (node (ref "R68") (pin "1") (pinfunction "1_1") (pintype "passive"))
      (node (ref "R69") (pin "1") (pinfunction "1_1") (pintype "passive"))
      (node (ref "R70") (pin "2") (pinfunction "2_2") (pintype "passive"))
      (node (ref "R71") (pin "2") (pinfunction "2_2") (pintype "passive"))
      (node (ref "U16") (pin "17") (pinfunction "GND_17") (pintype "passive"))
      (node (ref "U16") (pin "25") (pinfunction "Thermal_Pad_25") (pintype "passive"))
      (node (ref "U3") (pin "11") (pinfunction "RTN_11") (pintype "passive"))
      (node (ref "U3") (pin "12") (pinfunction "RTN_12") (pintype "passive"))
    )
    (net (code "22") (name "Net-(C57-Pad1)") (class "Default")
      (node (ref "C57") (pin "1") (pinfunction "1_1") (pintype "passive"))
      (node (ref "J15") (pin "1") (pinfunction "1_1") (pintype "passive"))
      (node (ref "Q1") (pin "D") (pinfunction "D_D") (pintype "passive"))
    )
    (net (code "23") (name "Net-(C84-Pad1)") (class "Default")
      (node (ref "C84") (pin "1") (pinfunction "1_1") (pintype "passive"))
      (node (ref "Q10") (pin "G") (pinfunction "G_G") (pintype "passive"))
      (node (ref "R48") (pin "1") (pinfunction "1_1") (pintype "passive"))
      (node (ref "R53") (pin "1") (pinfunction "1_1") (pintype "passive"))
    )
    (net (code "24") (name "Net-(C86-Pad1)") (class "Default")
      (node (ref "C86") (pin "1") (pinfunction "1_1") (pintype "passive"))
      (node (ref "Q5") (pin "G") (pinfunction "G_G") (pintype "passive"))
      (node (ref "Q6") (pin "G") (pinfunction "G_G") (pintype "passive"))
      (node (ref "R52") (pin "1") (pinfunction "1_1") (pintype "passive"))
      (node (ref "R54") (pin "1") (pinfunction "1_1") (pintype "passive"))
    )
    (net (code "25") (name "Net-(C89-Pad2)") (class "Default")
      (node (ref "C89") (pin "2") (pinfunction "2_2") (pintype "passive"))
      (node (ref "R50") (pin "1") (pinfunction "1_1") (pintype "passive"))
    )
    (net (code "26") (name "Net-(CD1-Pad1)") (class "Default")
      (node (ref "CD1") (pin "1") (pinfunction "1_1") (pintype "passive"))
      (node (ref "CD2") (pin "1") (pinfunction "1_1") (pintype "passive"))
      (node (ref "FB1") (pin "1") (pinfunction "1_1") (pintype "passive"))
    )
    (net (code "27") (name "Net-(CD1-Pad4)") (class "Default")
      (node (ref "CD1") (pin "4") (pinfunction "4_4") (pintype "passive"))
      (node (ref "CD2") (pin "4") (pinfunction "4_4") (pintype "passive"))
      (node (ref "FB2") (pin "1") (pinfunction "1_1") (pintype "passive"))
    )
    (net (code "28") (name "Net-(D7-PadA)") (class "Default")
      (node (ref "D7") (pin "A") (pinfunction "A_A") (pintype "passive"))
      (node (ref "R5") (pin "2") (pinfunction "2_2") (pintype "passive"))
    )
    (net (code "29") (name "Net-(D9-Pad1)") (class "Default")
      (node (ref "D9") (pin "1") (pinfunction "1_1") (pintype "passive"))
      (node (ref "R55") (pin "1") (pinfunction "1_1") (pintype "passive"))
    )
    (net (code "30") (name "Net-(D11-Pad1)") (class "Default")
      (node (ref "D11") (pin "1") (pinfunction "1_1") (pintype "passive"))
      (node (ref "R59") (pin "1") (pinfunction "1_1") (pintype "passive"))
    )
    (net (code "31") (name "Net-(D12-Pad1)") (class "Default")
      (node (ref "D12") (pin "1") (pinfunction "1_1") (pintype "passive"))
      (node (ref "R64") (pin "1") (pinfunction "1_1") (pintype "passive"))
    )
    (net (code "32") (name "Net-(D14-A)") (class "Default")
      (node (ref "D14") (pin "1") (pinfunction "A_1") (pintype "passive"))
      (node (ref "Q2") (pin "S") (pinfunction "S_S") (pintype "passive"))
      (node (ref "R82") (pin "2") (pinfunction "2_2") (pintype "passive"))
    )
    (net (code "33") (name "Net-(D15-A)") (class "Default")
      (node (ref "D15") (pin "1") (pinfunction "A_1") (pintype "passive"))
      (node (ref "Q3") (pin "S") (pinfunction "S_S") (pintype "passive"))
      (node (ref "R85") (pin "2") (pinfunction "2_2") (pintype "passive"))
    )
    (net (code "34") (name "Net-(Q1-PadG)") (class "Default")
      (node (ref "Q1") (pin "G") (pinfunction "G_G") (pintype "passive"))
      (node (ref "Q4") (pin "1") (pinfunction "1_1") (pintype "passive"))
      (node (ref "R14") (pin "2") (pinfunction "2_2") (pintype "passive"))
    )
    (net (code "35") (name "Net-(Q11-B)") (class "Default")
      (node (ref "Q11") (pin "2") (pinfunction "B_2") (pintype "passive"))
      (node (ref "R84") (pin "2") (pinfunction "2_2") (pintype "passive"))
    )
    (net (code "36") (name "Net-(Q11-C)") (class "Default")
      (node (ref "Q11") (pin "3") (pinfunction "C_3") (pintype "passive"))
      (node (ref "Q2") (pin "G") (pinfunction "G_G") (pintype "passive"))
      (node (ref "R82") (pin "1") (pinfunction "1_1") (pintype "passive"))
      (node (ref "R83") (pin "2") (pinfunction "2_2") (pintype "passive"))
    )
    (net (code "37") (name "Net-(Q12-B)") (class "Default")
      (node (ref "Q12") (pin "2") (pinfunction "B_2") (pintype "passive"))
      (node (ref "R87") (pin "2") (pinfunction "2_2") (pintype "passive"))
    )
    (net (code "38") (name "Net-(Q12-C)") (class "Default")
      (node (ref "Q12") (pin "3") (pinfunction "C_3") (pintype "passive"))
      (node (ref "Q3") (pin "G") (pinfunction "G_G") (pintype "passive"))
      (node (ref "R85") (pin "1") (pinfunction "1_1") (pintype "passive"))
      (node (ref "R86") (pin "2") (pinfunction "2_2") (pintype "passive"))
    )
    (net (code "39") (name "Net-(R46-Pad2)") (class "Default")
      (node (ref "R46") (pin "2") (pinfunction "2_2") (pintype "passive"))
      (node (ref "R47") (pin "2") (pinfunction "2_2") (pintype "passive"))
      (node (ref "R51") (pin "1") (pinfunction "1_1") (pintype "passive"))
      (node (ref "RT1") (pin "1") (pinfunction "1_1") (pintype "passive"))
    )
    (net (code "40") (name "Net-(U3-AMPS_CTL)") (class "Default")
      (node (ref "R41") (pin "1") (pinfunction "1_1") (pintype "passive"))
      (node (ref "U3") (pin "8") (pinfunction "AMPS_CTL_8") (pintype "passive"))
    )
    (net (code "41") (name "Net-(U3-BT_N)") (class "Default")
      (node (ref "R42") (pin "1") (pinfunction "1_1") (pintype "passive"))
      (node (ref "U3") (pin "19") (pinfunction "BT_N_19") (pintype "passive"))
    )
    (net (code "42") (name "Net-(U3-CLSA)") (class "Default")
      (node (ref "R10") (pin "1") (pinfunction "1_1") (pintype "passive"))
      (node (ref "U3") (pin "3") (pinfunction "CLSA_3") (pintype "passive"))
    )
    (net (code "43") (name "Net-(U3-CLSB)") (class "Default")
      (node (ref "R11") (pin "1") (pinfunction "1_1") (pintype "passive"))
      (node (ref "U3") (pin "6") (pinfunction "CLSB_6") (pintype "passive"))
    )
    (net (code "44") (name "Net-(U3-DEN)") (class "Default")
      (node (ref "R6") (pin "1") (pinfunction "1_1") (pintype "passive"))
      (node (ref "U3") (pin "2") (pinfunction "DEN_2") (pintype "passive"))
    )
    (net (code "45") (name "Net-(U3-MPS_DUTY)") (class "Default")
      (node (ref "R43") (pin "1") (pinfunction "1_1") (pintype "passive"))
      (node (ref "U3") (pin "9") (pinfunction "MPS_DUTY_9") (pintype "passive"))
    )
    (net (code "46") (name "Net-(U3-REF)") (class "Default")
      (node (ref "R39") (pin "1") (pinfunction "1_1") (pintype "passive"))
      (node (ref "U3") (pin "7") (pinfunction "REF_7") (pintype "passive"))
    )
    (net (code "47") (name "Net-(U3-TPH)") (class "Default")
      (node (ref "R34") (pin "1") (pinfunction "1_1") (pintype "passive"))
      (node (ref "U3") (pin "18") (pinfunction "TPH_18") (pintype "passive"))
    )
    (net (code "48") (name "Net-(U3-TPL)") (class "Default")
      (node (ref "R35") (pin "1") (pinfunction "1_1") (pintype "passive"))
      (node (ref "U3") (pin "17") (pinfunction "TPL_17") (pintype "passive"))
    )
    (net (code "49") (name "Net-(U12-ANODE)") (class "Default")
      (node (ref "R44") (pin "2") (pinfunction "2_2") (pintype "passive"))
      (node (ref "U12") (pin "1") (pinfunction "ANODE_1") (pintype "passive"))
    )
    (net (code "50") (name "Net-(U12-CATHODE)") (class "Default")
      (node (ref "R68") (pin "2") (pinfunction "2_2") (pintype "passive"))
      (node (ref "U12") (pin "2") (pinfunction "CATHODE_2") (pintype "passive"))
    )
    (net (code "51") (name "Net-(U12-EMITTRE)") (class "Default")
      (node (ref "R69") (pin "2") (pinfunction "2_2") (pintype "passive"))
      (node (ref "U12") (pin "3") (pinfunction "EMITTRE_3") (pintype "passive"))
    )
    (net (code "52") (name "Net-(U16-ACP)") (class "Default")
      (node (ref "C85") (pin "1") (pinfunction "1_1") (pintype "passive"))
      (node (ref "C87") (pin "2") (pinfunction "2_2") (pintype "passive"))
      (node (ref "Q6") (pin "D") (pinfunction "D_D") (pintype "passive"))
      (node (ref "RAC") (pin "1") (pinfunction "1_1") (pintype "passive"))
      (node (ref "U16") (pin "2") (pinfunction "ACP_2") (pintype "passive"))
    )
    (net (code "53") (name "Net-(U16-BTST)") (class "Default")
      (node (ref "C97") (pin "2") (pinfunction "2_2") (pintype "passive"))
      (node (ref "D10") (pin "2") (pinfunction "2_2") (pintype "passive"))
      (node (ref "U16") (pin "22") (pinfunction "BTST_22") (pintype "passive"))
    )
    (net (code "54") (name "Net-(U16-REGN)") (class "Default")
      (node (ref "C101") (pin "1") (pinfunction "1_1") (pintype "passive"))
      (node (ref "D10") (pin "1") (pinfunction "1_1") (pintype "passive"))
      (node (ref "U16") (pin "18") (pinfunction "REGN_18") (pintype "passive"))
    )
    (net (code "55") (name "Net-(U16-TTC)") (class "Default")
      (node (ref "Cttc") (pin "1") (pinfunction "1_1") (pintype "passive"))
      (node (ref "U16") (pin "7") (pinfunction "TTC_7") (pintype "passive"))
    )
    (net (code "56") (name "Net-(U16-VCC)") (class "Default")
      (node (ref "C81") (pin "1") (pinfunction "1_1") (pintype "passive"))
      (node (ref "R45") (pin "2") (pinfunction "2_2") (pintype "passive"))
      (node (ref "U16") (pin "24") (pinfunction "VCC_24") (pintype "passive"))
    )
    (net (code "57") (name "Net-(U16-~{ACDRV})") (class "Default")
      (node (ref "R54") (pin "2") (pinfunction "2_2") (pintype "passive"))
      (node (ref "U16") (pin "3") (pinfunction "~{ACDRV}_3") (pintype "passive"))
    )
    (net (code "58") (name "Net-(U16-~{BATDRV})") (class "Default")
      (node (ref "R53") (pin "2") (pinfunction "2_2") (pintype "passive"))
      (node (ref "U16") (pin "23") (pinfunction "~{BATDRV}_23") (pintype "passive"))
    )
    (net (code "59") (name "PR12") (class "Default")
      (node (ref "CD1") (pin "2") (pinfunction "2_2") (pintype "passive"))
    )
    (net (code "60") (name "PR36") (class "Default")
      (node (ref "CD1") (pin "3") (pinfunction "3_3") (pintype "passive"))
    )
    (net (code "61") (name "PR45") (class "Default")
      (node (ref "CD2") (pin "2") (pinfunction "2_2") (pintype "passive"))
    )
    (net (code "62") (name "PR78") (class "Default")
      (node (ref "CD2") (pin "3") (pinfunction "3_3") (pintype "passive"))
    )
    (net (code "63") (name "P_VDD") (class "Default")
      (node (ref "C79") (pin "1") (pinfunction "1_1") (pintype "passive"))
      (node (ref "C80") (pin "1") (pinfunction "1_1") (pintype "passive"))
      (node (ref "C95") (pin "1") (pinfunction "1_1") (pintype "passive"))
      (node (ref "D8") (pin "2") (pinfunction "K_2") (pintype "passive"))
      (node (ref "FB1") (pin "2") (pinfunction "2_2") (pintype "passive"))
      (node (ref "PS1") (pin "1") (pinfunction "+VIN_1") (pintype "passive"))
      (node (ref "R34") (pin "2") (pinfunction "2_2") (pintype "passive"))
      (node (ref "R35") (pin "2") (pinfunction "2_2") (pintype "passive"))
      (node (ref "R37") (pin "1") (pinfunction "1_1") (pintype "passive"))
      (node (ref "R38") (pin "1") (pinfunction "1_1") (pintype "passive"))
      (node (ref "R42") (pin "2") (pinfunction "2_2") (pintype "passive"))
      (node (ref "R5") (pin "1") (pinfunction "1_1") (pintype "passive"))
      (node (ref "R6") (pin "2") (pinfunction "2_2") (pintype "passive"))
      (node (ref "U3") (pin "1") (pinfunction "VDD_1") (pintype "passive"))
    )
    (net (code "64") (name "VBAT") (class "Default")
      (node (ref "C90") (pin "1") (pinfunction "1_1") (pintype "passive"))
      (node (ref "C91") (pin "1") (pinfunction "1_1") (pintype "passive"))
      (node (ref "C92") (pin "1") (pinfunction "1_1") (pintype "passive"))
      (node (ref "C96") (pin "1") (pinfunction "1_1") (pintype "passive"))
      (node (ref "C99") (pin "1") (pinfunction "1_1") (pintype "passive"))
      (node (ref "Cff1") (pin "2") (pinfunction "2_2") (pintype "passive"))
      (node (ref "J19") (pin "1") (pinfunction "1_1") (pintype "passive"))
      (node (ref "Q10") (pin "S") (pinfunction "S_S") (pintype "passive"))
      (node (ref "R65") (pin "2") (pinfunction "2_2") (pintype "passive"))
      (node (ref "RSR1") (pin "2") (pinfunction "2_2") (pintype "passive"))
      (node (ref "U16") (pin "13") (pinfunction "SRN_13") (pintype "passive"))
    )
    (net (code "65") (name "VIN") (class "Default")
      (node (ref "D14") (pin "2") (pinfunction "K_2") (pintype "passive"))
      (node (ref "D15") (pin "2") (pinfunction "K_2") (pintype "passive"))
      (node (ref "Q5") (pin "D") (pinfunction "D_D") (pintype "passive"))
      (node (ref "R50") (pin "2") (pinfunction "2_2") (pintype "passive"))
      (node (ref "R55") (pin "2") (pinfunction "2_2") (pintype "passive"))
      (node (ref "R59") (pin "2") (pinfunction "2_2") (pintype "passive"))
      (node (ref "R64") (pin "2") (pinfunction "2_2") (pintype "passive"))
    )
    (net (code "66") (name "VREF") (class "Default")
      (node (ref "C100") (pin "2") (pinfunction "2_2") (pintype "passive"))
      (node (ref "R46") (pin "1") (pinfunction "1_1") (pintype "passive"))
      (node (ref "R56") (pin "1") (pinfunction "1_1") (pintype "passive"))
      (node (ref "R57") (pin "1") (pinfunction "1_1") (pintype "passive"))
      (node (ref "R58") (pin "1") (pinfunction "1_1") (pintype "passive"))
      (node (ref "U16") (pin "10") (pinfunction "VREF_10") (pintype "passive"))
      (node (ref "U16") (pin "4") (pinfunction "CE_4") (pintype "passive"))
    )
    (net (code "67") (name "VSS") (class "Default")
      (node (ref "C95") (pin "2") (pinfunction "2_2") (pintype "passive"))
      (node (ref "D8") (pin "1") (pinfunction "A_1") (pintype "passive"))
      (node (ref "FB2") (pin "2") (pinfunction "2_2") (pintype "passive"))
      (node (ref "R10") (pin "2") (pinfunction "2_2") (pintype "passive"))
      (node (ref "R11") (pin "2") (pinfunction "2_2") (pintype "passive"))
      (node (ref "R39") (pin "2") (pinfunction "2_2") (pintype "passive"))
      (node (ref "R41") (pin "2") (pinfunction "2_2") (pintype "passive"))
      (node (ref "R43") (pin "2") (pinfunction "2_2") (pintype "passive"))
      (node (ref "U3") (pin "21") (pinfunction "VSS_21") (pintype "passive"))
      (node (ref "U3") (pin "4") (pinfunction "VSS_4") (pintype "passive"))
      (node (ref "U3") (pin "5") (pinfunction "VSS_5") (pintype "passive"))
    )
    (net (code "68") (name "unconnected-(D10-Pad3)") (class "Default")
      (node (ref "D10") (pin "3") (pinfunction "3_3") (pintype "passive+no_connect"))
    )
    (net (code "69") (name "unconnected-(PS1--SENSE_IN-Pad5)") (class "Default")
      (node (ref "PS1") (pin "5") (pinfunction "-SENSE_IN_5") (pintype "passive+no_connect"))
    )
    (net (code "70") (name "unconnected-(PS1-TRIM-Pad6)") (class "Default")
      (node (ref "PS1") (pin "6") (pinfunction "TRIM_6") (pintype "passive+no_connect"))
    )
    (net (code "71") (name "unconnected-(Q4-Pad2)") (class "Default")
      (node (ref "Q4") (pin "2") (pinfunction "2_2") (pintype "passive+no_connect"))
    )
    (net (code "72") (name "unconnected-(U3-AUTCLS_N-Pad10)") (class "Default")
      (node (ref "U3") (pin "10") (pinfunction "AUTCLS_N_10") (pintype "passive+no_connect"))
    )
    (net (code "73") (name "unconnected-(U3-IRSHDL_EN-Pad16)") (class "Default")
      (node (ref "U3") (pin "16") (pinfunction "IRSHDL_EN_16") (pintype "passive+no_connect"))
    )
    (net (code "74") (name "unconnected-(U3-NC-Pad14)") (class "Default")
      (node (ref "U3") (pin "14") (pinfunction "NC_14") (pintype "passive+no_connect"))
    )
    (net (code "75") (name "unconnected-(U3-NC-Pad15)") (class "Default")
      (node (ref "U3") (pin "15") (pinfunction "NC_15") (pintype "passive+no_connect"))
    )
    (net (code "76") (name "unconnected-(U3-NC-Pad20)") (class "Default")
      (node (ref "U3") (pin "20") (pinfunction "NC_20") (pintype "passive+no_connect"))
    )
  )
)
